# 01-POWER.net
KiCad netlist of a schematic drawn in Altium Designer
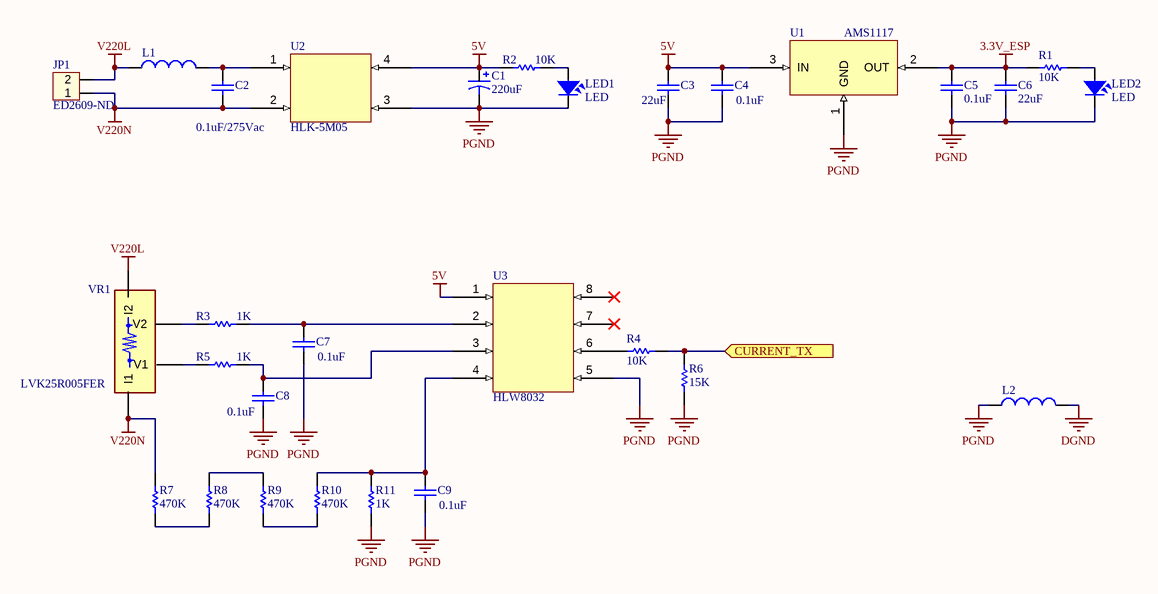
[diagram p0: 01-POWER.SchDoc]

(export (version "E")
  (design (tool "Eeschema 10.0.6"))
  (components
    (comp (ref "C1")
      (value "220uF")
      (footprint "CAP ALU CASE G SMD")
      (description "CAP ALU 220UF 20% 50V SMD")
      (fields
        (field (name "MANUFACTURER") "Nichicon")
        (field (name "MANUFACTURER PART NUMBER") "UPW1J331MHD")
      )
      (libsource (lib "GSHT_181013") (part "330uF/50V/ALU12.5X20mm/20%/7000Hrs"))
    )
    (comp (ref "C2")
      (value "0.1uF/275Vac")
      (footprint "CAP_CERA_C2012(CC0805INCH)")
      (fields (field (name "MANUFACTURER") "Murata"))
      (libsource (lib "GSHT_181013") (part "0.1uF/50V/C0603/10%"))
    )
    (comp (ref "C3")
      (value "22uF")
      (footprint "CAP_CERA_C2012(CC0805INCH)")
      (description "22µF ±20% 25V Ceramic Capacitor X5R 0805 (2012 Metric)")
      (fields (field (name "MANUFACTURER") "Tariff Applied"))
      (libsource (lib "GSHT_181013") (part "0.1uF/50V/C0603/10%"))
    )
    (comp (ref "C4")
      (value "0.1uF")
      (footprint "CAP_CERA_C2012(CC0805INCH)")
      (description "0.1µF ±10% 25V Ceramic Capacitor X7R 0805 (2012 Metric)")
      (libsource (lib "GSHT_181013") (part "0.1uF/50V/C0603/10%"))
    )
    (comp (ref "C5")
      (value "0.1uF")
      (footprint "CAP_CERA_C2012(CC0805INCH)")
      (description "0.1µF ±10% 25V Ceramic Capacitor X7R 0805 (2012 Metric)")
      (libsource (lib "GSHT_181013") (part "0.1uF/50V/C0603/10%"))
    )
    (comp (ref "C6")
      (value "22uF")
      (footprint "CAP_CERA_C2012(CC0805INCH)")
      (description "22µF ±20% 25V Ceramic Capacitor X5R 0805 (2012 Metric)")
      (fields (field (name "MANUFACTURER") "Tariff Applied"))
      (libsource (lib "GSHT_181013") (part "0.1uF/50V/C0603/10%"))
    )
    (comp (ref "C7")
      (value "0.1uF")
      (footprint "Cap Ceramic 0603 SMD")
      (description "CAP CER 0.1UF 50V 10% X7R 0603")
      (fields
        (field (name "MANUFACTURER") "Murata Electronics North America")
        (field (name "MANUFACTURER PART NUMBER") "GRM188R71H104KA93D")
      )
      (libsource (lib "GSHT_181013") (part "0.1uF/50V/C0603/10%"))
    )
    (comp (ref "C8")
      (value "0.1uF")
      (footprint "Cap Ceramic 0603 SMD")
      (description "CAP CER 0.1UF 50V 10% X7R 0603")
      (fields
        (field (name "MANUFACTURER") "Murata Electronics North America")
        (field (name "MANUFACTURER PART NUMBER") "GRM188R71H104KA93D")
      )
      (libsource (lib "GSHT_181013") (part "0.1uF/50V/C0603/10%"))
    )
    (comp (ref "C9")
      (value "0.1uF")
      (footprint "Cap Ceramic 0603 SMD")
      (description "CAP CER 0.1UF 50V 10% X7R 0603")
      (fields
        (field (name "MANUFACTURER") "Murata Electronics North America")
        (field (name "MANUFACTURER PART NUMBER") "GRM188R71H104KA93D")
      )
      (libsource (lib "GSHT_181013") (part "0.1uF/50V/C0603/10%"))
    )
    (comp (ref "JP1")
      (value "ED2609-ND")
      (footprint "DOMINO_OSTTC_2P")
      (description "2 Position Wire to Board Terminal Block Horizontal with Board 0.200\" (5.08mm) Through Hole")
      (libsource (lib "lpson") (part "Con2"))
    )
    (comp (ref "L1")
      (value "ASPI-7318-8R2M-TCT-ND")
      (footprint "ASPI-7318-8R2M-TCT-ND")
      (description "Sensible value10-15mH，current\r\n70-500mA")
      (libsource (lib "lpson") (part "Inductor"))
    )
    (comp (ref "L2")
      (value "ASPI-7318-8R2M-TCT-ND")
      (footprint "ASPI-7318-8R2M-TCT-ND")
      (description "Sensible value10-15mH，current\r\n70-500mA")
      (libsource (lib "lpson") (part "Inductor"))
    )
    (comp (ref "LED1")
      (value "LED")
      (footprint "LED5R")
      (description "LED Single colour Green and Red")
      (libsource (lib "lpson") (part "LED"))
    )
    (comp (ref "LED2")
      (value "LED")
      (footprint "LED5R")
      (description "LED Single colour Green and Red")
      (libsource (lib "lpson") (part "LED"))
    )
    (comp (ref "R1")
      (value "10K")
      (footprint "Res 0603 SMD")
      (description "RES SMD 10K OHM 1% 1/10W 0603")
      (fields
        (field (name "MANUFACTURER") "Yageo")
        (field (name "MANUFACTURER PART NUMBER") "RC0603FR-0715KL")
      )
      (libsource (lib "GSHT_181013") (part "15K/R0603/1%"))
    )
    (comp (ref "R2")
      (value "10K")
      (footprint "Res 0603 SMD")
      (description "RES SMD 10K OHM 1% 1/10W 0603")
      (fields
        (field (name "MANUFACTURER") "Yageo")
        (field (name "MANUFACTURER PART NUMBER") "RC0603FR-0715KL")
      )
      (libsource (lib "GSHT_181013") (part "15K/R0603/1%"))
    )
    (comp (ref "R3")
      (value "1K")
      (footprint "Res 0603 SMD")
      (description "RES SMD 1K OHM 1% 1/10W 0603")
      (fields
        (field (name "MANUFACTURER") "Yageo")
        (field (name "MANUFACTURER PART NUMBER") "RC0603FR-0715KL")
      )
      (libsource (lib "GSHT_181013") (part "15K/R0603/1%"))
    )
    (comp (ref "R4")
      (value "10K")
      (footprint "Res 0603 SMD")
      (description "RES SMD 10K OHM 1% 1/10W 0603")
      (fields
        (field (name "MANUFACTURER") "Yageo")
        (field (name "MANUFACTURER PART NUMBER") "RC0603FR-0715KL")
      )
      (libsource (lib "GSHT_181013") (part "15K/R0603/1%"))
    )
    (comp (ref "R5")
      (value "1K")
      (footprint "Res 0603 SMD")
      (description "RES SMD 1K OHM 1% 1/10W 0603")
      (fields
        (field (name "MANUFACTURER") "Yageo")
        (field (name "MANUFACTURER PART NUMBER") "RC0603FR-0715KL")
      )
      (libsource (lib "GSHT_181013") (part "15K/R0603/1%"))
    )
    (comp (ref "R6")
      (value "15K")
      (footprint "Res 0603 SMD")
      (description "RES SMD 15K OHM 1% 1/10W 0603")
      (fields
        (field (name "MANUFACTURER") "Yageo")
        (field (name "MANUFACTURER PART NUMBER") "RC0603FR-0715KL")
      )
      (libsource (lib "GSHT_181013") (part "15K/R0603/1%"))
    )
    (comp (ref "R7")
      (value "470K")
      (footprint "Res 0603 SMD")
      (description "RES SMD 470K OHM 1% 1/10W 0603")
      (fields
        (field (name "MANUFACTURER") "Yageo")
        (field (name "MANUFACTURER PART NUMBER") "RC0603FR-0715KL")
      )
      (libsource (lib "GSHT_181013") (part "15K/R0603/1%"))
    )
    (comp (ref "R8")
      (value "470K")
      (footprint "Res 0603 SMD")
      (description "RES SMD 470K OHM 1% 1/10W 0603")
      (fields
        (field (name "MANUFACTURER") "Yageo")
        (field (name "MANUFACTURER PART NUMBER") "RC0603FR-0715KL")
      )
      (libsource (lib "GSHT_181013") (part "15K/R0603/1%"))
    )
    (comp (ref "R9")
      (value "470K")
      (footprint "Res 0603 SMD")
      (description "RES SMD 470K OHM 1% 1/10W 0603")
      (fields
        (field (name "MANUFACTURER") "Yageo")
        (field (name "MANUFACTURER PART NUMBER") "RC0603FR-0715KL")
      )
      (libsource (lib "GSHT_181013") (part "15K/R0603/1%"))
    )
    (comp (ref "R10")
      (value "470K")
      (footprint "Res 0603 SMD")
      (description "RES SMD 470K OHM 1% 1/10W 0603")
      (fields
        (field (name "MANUFACTURER") "Yageo")
        (field (name "MANUFACTURER PART NUMBER") "RC0603FR-0715KL")
      )
      (libsource (lib "GSHT_181013") (part "15K/R0603/1%"))
    )
    (comp (ref "R11")
      (value "1K")
      (footprint "Res 0603 SMD")
      (description "RES SMD 1K OHM 1% 1/10W 0603")
      (fields
        (field (name "MANUFACTURER") "Yageo")
        (field (name "MANUFACTURER PART NUMBER") "RC0603FR-0715KL")
      )
      (libsource (lib "GSHT_181013") (part "15K/R0603/1%"))
    )
    (comp (ref "U1") (value "AMS1117") (libsource (lib "Schlib1") (part "AMS1117")))
    (comp (ref "U2")
      (value "HLK-5M05")
      (footprint "CONV_HLK-5M05")
      (libsource (lib "Schlib1") (part "HLK-5M05"))
    )
    (comp (ref "U3")
      (value "HLW8032")
      (footprint "SOIC127P600X175-8N")
      (libsource (lib "Schlib1") (part "HLW8032"))
    )
    (comp (ref "VR1")
      (value "LVK25R005FER")
      (footprint "LVK25R005FER")
      (description "Resistor")
      (fields
        (field (name "MOUSER PART NUMBER") "588-LVK25R005FER")
        (field (name "RS PART NUMBER") "8934005")
      )
      (libsource (lib "MySchlib") (part "LVK25R005FER"))
    )
  )
  (nets
    (net (code "1") (name "/CURRENT_TX") (class "Default")
      (node (ref "R4") (pin "2") (pinfunction "2_2") (pintype "passive"))
      (node (ref "R6") (pin "1") (pinfunction "1_1") (pintype "passive"))
    )
    (net (code "2") (name "3.3V_ESP") (class "Default")
      (node (ref "C5") (pin "2") (pinfunction "2_2") (pintype "passive"))
      (node (ref "C6") (pin "2") (pinfunction "2_2") (pintype "passive"))
      (node (ref "R1") (pin "1") (pinfunction "1_1") (pintype "passive"))
      (node (ref "U1") (pin "2") (pinfunction "OUT_2") (pintype "input"))
    )
    (net (code "3") (name "5V") (class "Default")
      (node (ref "C1") (pin "1") (pinfunction "1_1") (pintype "passive"))
      (node (ref "C3") (pin "2") (pinfunction "2_2") (pintype "passive"))
      (node (ref "C4") (pin "2") (pinfunction "2_2") (pintype "passive"))
      (node (ref "R2") (pin "1") (pinfunction "1_1") (pintype "passive"))
      (node (ref "U1") (pin "3") (pinfunction "IN_3") (pintype "input"))
      (node (ref "U2") (pin "4") (pintype "input"))
      (node (ref "U3") (pin "1") (pintype "input"))
    )
    (net (code "4") (name "DGND") (class "Default")
      (node (ref "L2") (pin "2") (pinfunction "2_2") (pintype "passive"))
    )
    (net (code "5") (name "Net-(C2-Pad2)") (class "Default")
      (node (ref "C2") (pin "2") (pinfunction "2_2") (pintype "passive"))
      (node (ref "L1") (pin "2") (pinfunction "2_2") (pintype "passive"))
      (node (ref "U2") (pin "1") (pintype "input"))
    )
    (net (code "6") (name "Net-(C7-Pad2)") (class "Default")
      (node (ref "C7") (pin "2") (pinfunction "2_2") (pintype "passive"))
      (node (ref "R3") (pin "1") (pinfunction "1_1") (pintype "passive"))
      (node (ref "U3") (pin "2") (pintype "input"))
    )
    (net (code "7") (name "Net-(C8-Pad2)") (class "Default")
      (node (ref "C8") (pin "2") (pinfunction "2_2") (pintype "passive"))
      (node (ref "R5") (pin "1") (pinfunction "1_1") (pintype "passive"))
      (node (ref "U3") (pin "3") (pintype "input"))
    )
    (net (code "8") (name "Net-(C9-Pad2)") (class "Default")
      (node (ref "C9") (pin "2") (pinfunction "2_2") (pintype "passive"))
      (node (ref "R10") (pin "1") (pinfunction "1_1") (pintype "passive"))
      (node (ref "R11") (pin "2") (pinfunction "2_2") (pintype "passive"))
      (node (ref "U3") (pin "4") (pintype "input"))
    )
    (net (code "9") (name "Net-(LED1-Pad1)") (class "Default")
      (node (ref "LED1") (pin "1") (pinfunction "1_1") (pintype "passive"))
      (node (ref "R2") (pin "2") (pinfunction "2_2") (pintype "passive"))
    )
    (net (code "10") (name "Net-(LED2-Pad1)") (class "Default")
      (node (ref "LED2") (pin "1") (pinfunction "1_1") (pintype "passive"))
      (node (ref "R1") (pin "2") (pinfunction "2_2") (pintype "passive"))
    )
    (net (code "11") (name "Net-(R4-Pad1)") (class "Default")
      (node (ref "R4") (pin "1") (pinfunction "1_1") (pintype "passive"))
      (node (ref "U3") (pin "6") (pintype "input"))
    )
    (net (code "12") (name "Net-(R7-Pad2)") (class "Default")
      (node (ref "R7") (pin "2") (pinfunction "2_2") (pintype "passive"))
      (node (ref "R8") (pin "2") (pinfunction "2_2") (pintype "passive"))
    )
    (net (code "13") (name "Net-(R8-Pad1)") (class "Default")
      (node (ref "R8") (pin "1") (pinfunction "1_1") (pintype "passive"))
      (node (ref "R9") (pin "1") (pinfunction "1_1") (pintype "passive"))
    )
    (net (code "14") (name "Net-(R10-Pad2)") (class "Default")
      (node (ref "R10") (pin "2") (pinfunction "2_2") (pintype "passive"))
      (node (ref "R9") (pin "2") (pinfunction "2_2") (pintype "passive"))
    )
    (net (code "15") (name "Net-(VR1-V1)") (class "Default")
      (node (ref "R5") (pin "2") (pinfunction "2_2") (pintype "passive"))
      (node (ref "VR1") (pin "3") (pinfunction "V1_3") (pintype "passive"))
    )
    (net (code "16") (name "Net-(VR1-V2)") (class "Default")
      (node (ref "R3") (pin "2") (pinfunction "2_2") (pintype "passive"))
      (node (ref "VR1") (pin "4") (pinfunction "V2_4") (pintype "passive"))
    )
    (net (code "17") (name "PGND") (class "Default")
      (node (ref "C1") (pin "2") (pinfunction "2_2") (pintype "passive"))
      (node (ref "C3") (pin "1") (pinfunction "1_1") (pintype "passive"))
      (node (ref "C4") (pin "1") (pinfunction "1_1") (pintype "passive"))
      (node (ref "C5") (pin "1") (pinfunction "1_1") (pintype "passive"))
      (node (ref "C6") (pin "1") (pinfunction "1_1") (pintype "passive"))
      (node (ref "C7") (pin "1") (pinfunction "1_1") (pintype "passive"))
      (node (ref "C8") (pin "1") (pinfunction "1_1") (pintype "passive"))
      (node (ref "C9") (pin "1") (pinfunction "1_1") (pintype "passive"))
      (node (ref "L2") (pin "1") (pinfunction "1_1") (pintype "passive"))
      (node (ref "LED1") (pin "2") (pinfunction "2_2") (pintype "passive"))
      (node (ref "LED2") (pin "2") (pinfunction "2_2") (pintype "passive"))
      (node (ref "R11") (pin "1") (pinfunction "1_1") (pintype "passive"))
      (node (ref "R6") (pin "2") (pinfunction "2_2") (pintype "passive"))
      (node (ref "U1") (pin "1") (pinfunction "GND_1") (pintype "input"))
      (node (ref "U2") (pin "3") (pintype "input"))
      (node (ref "U3") (pin "5") (pintype "input"))
    )
    (net (code "18") (name "V220L") (class "Default")
      (node (ref "JP1") (pin "2") (pinfunction "2_2") (pintype "passive"))
      (node (ref "L1") (pin "1") (pinfunction "1_1") (pintype "passive"))
      (node (ref "VR1") (pin "2") (pinfunction "I2_2") (pintype "passive"))
    )
    (net (code "19") (name "V220N") (class "Default")
      (node (ref "C2") (pin "1") (pinfunction "1_1") (pintype "passive"))
      (node (ref "JP1") (pin "1") (pinfunction "1_1") (pintype "passive"))
      (node (ref "R7") (pin "1") (pinfunction "1_1") (pintype "passive"))
      (node (ref "U2") (pin "2") (pintype "input"))
      (node (ref "VR1") (pin "1") (pinfunction "I1_1") (pintype "passive"))
    )
    (net (code "20") (name "unconnected-(U3-Pad7)") (class "Default")
      (node (ref "U3") (pin "7") (pintype "input+no_connect"))
    )
    (net (code "21") (name "unconnected-(U3-Pad8)") (class "Default")
      (node (ref "U3") (pin "8") (pintype "input+no_connect"))
    )
  )
)
